# KELU1-0233.net
KiCad netlist of a schematic drawn in EAGLE
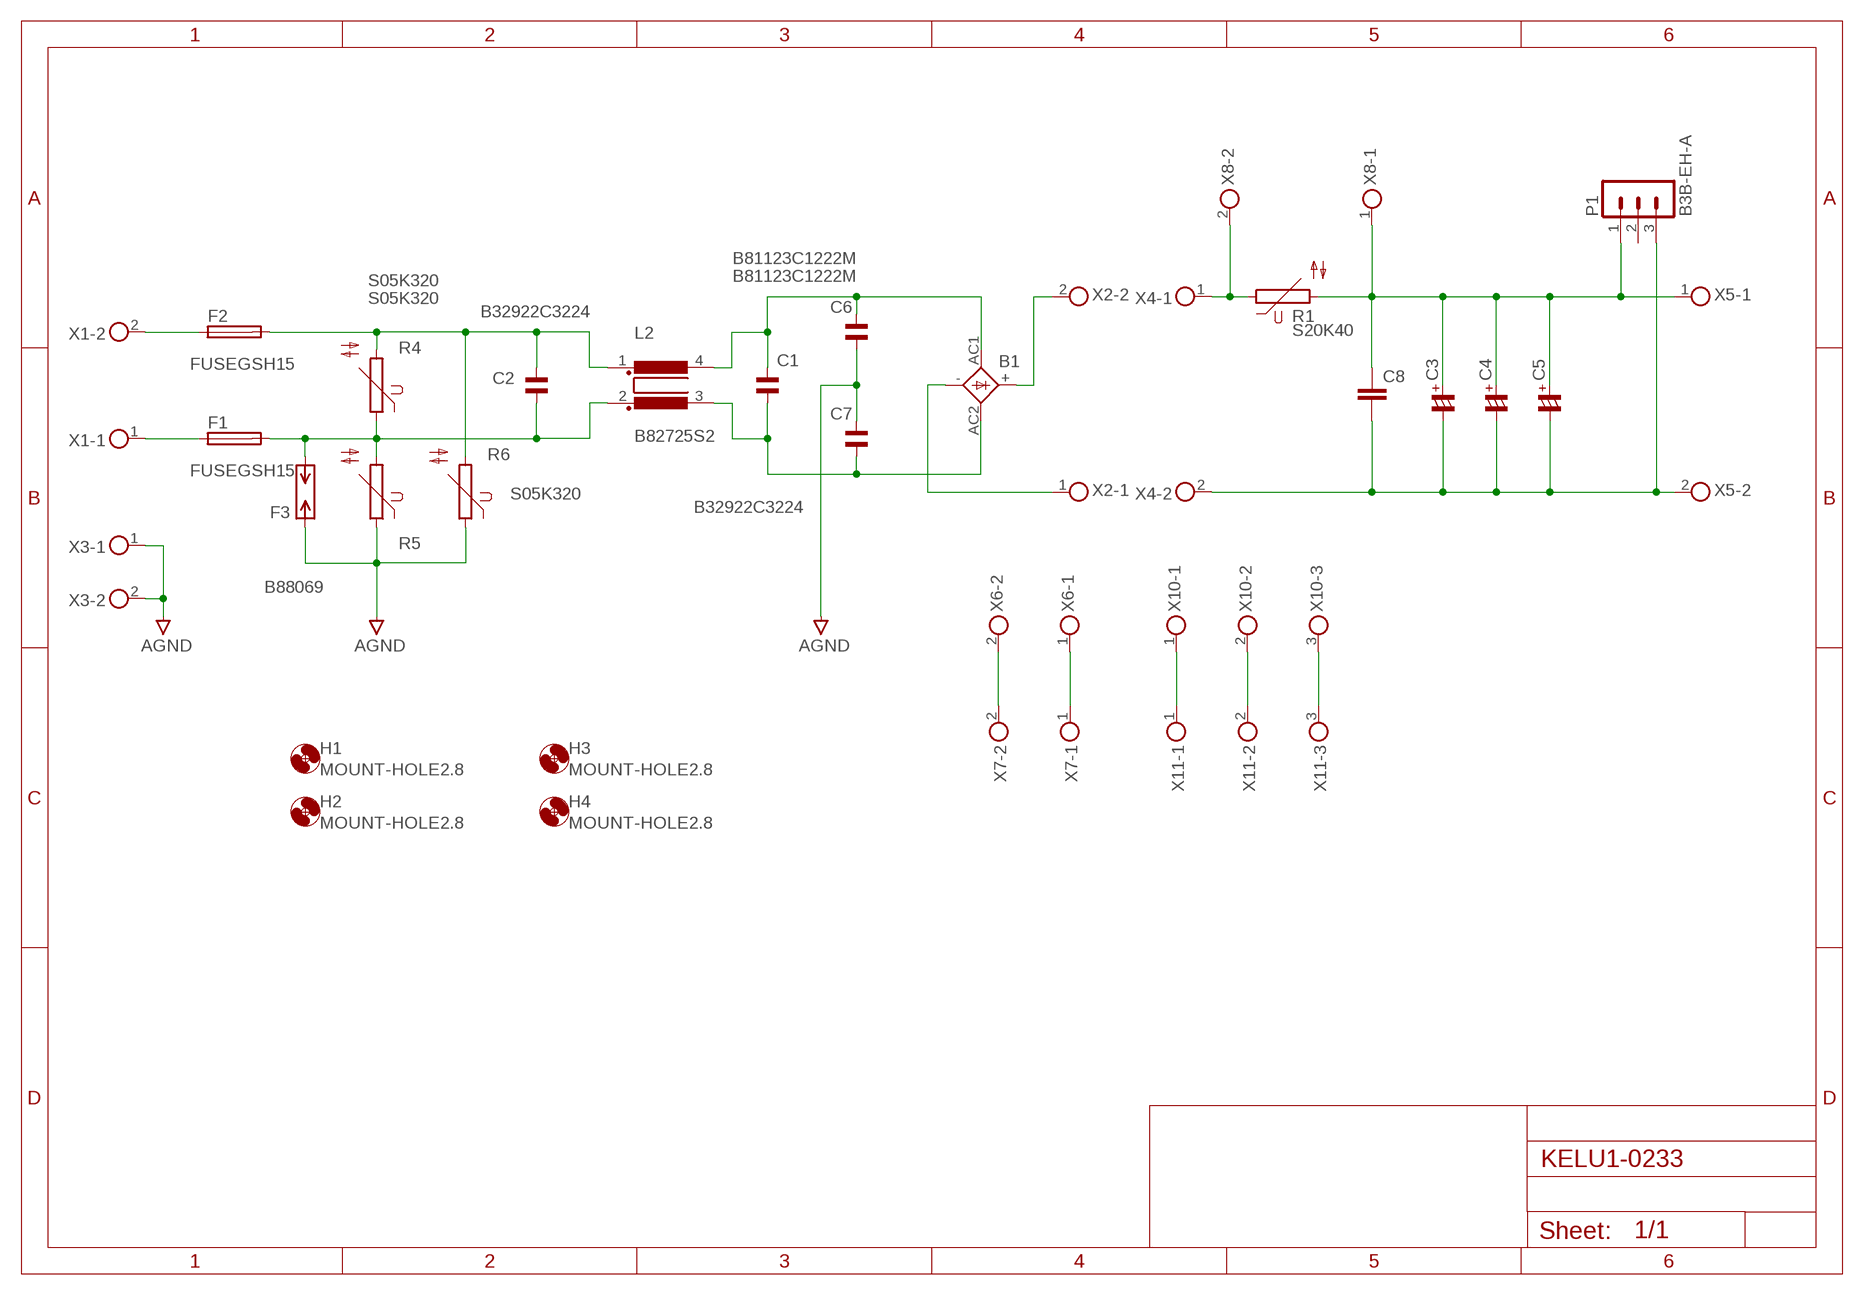
[diagram p0: schematic, sheet 1]

(export (version "E")
  (design (tool "Eeschema 10.0.6"))
  (components
    (comp (ref "B1")
      (value "FBM")
      (footprint "eagle-import:FBM")
      (libsource (lib "eagle-import") (part "FBM"))
    )
    (comp (ref "C1")
      (value "B32922C3224")
      (footprint "eagle-import:C150-054X183")
      (libsource (lib "eagle-import") (part "C-EU150-054X183"))
    )
    (comp (ref "C2")
      (value "B32922C3224")
      (footprint "eagle-import:C150-054X183")
      (libsource (lib "eagle-import") (part "C-EU150-054X183"))
    )
    (comp (ref "C3")
      (value "CPOL-EUE7.5-18")
      (footprint "eagle-import:E7,5-18")
      (libsource (lib "eagle-import") (part "CPOL-EUE7.5-18"))
    )
    (comp (ref "C4")
      (value "CPOL-EUE7.5-18")
      (footprint "eagle-import:E7,5-18")
      (libsource (lib "eagle-import") (part "CPOL-EUE7.5-18"))
    )
    (comp (ref "C5")
      (value "CPOL-EUE7.5-18")
      (footprint "eagle-import:E7,5-18")
      (libsource (lib "eagle-import") (part "CPOL-EUE7.5-18"))
    )
    (comp (ref "C6")
      (value "B81123C1222M")
      (footprint "eagle-import:C150-054X183")
      (libsource (lib "eagle-import") (part "C-EU150-054X183"))
    )
    (comp (ref "C7")
      (value "B81123C1222M")
      (footprint "eagle-import:C150-054X183")
      (libsource (lib "eagle-import") (part "C-EU150-054X183"))
    )
    (comp (ref "C8")
      (value "C-EU102-043X133")
      (footprint "eagle-import:C102-043X133")
      (libsource (lib "eagle-import") (part "resistor_C-EU102-043X133"))
    )
    (comp (ref "F1")
      (value "FUSEGSH15")
      (footprint "eagle-import:GSH15")
      (libsource (lib "eagle-import") (part "FUSEGSH15"))
    )
    (comp (ref "F2")
      (value "FUSEGSH15")
      (footprint "eagle-import:GSH15")
      (libsource (lib "eagle-import") (part "FUSEGSH15"))
    )
    (comp (ref "F3")
      (value "B88069")
      (footprint "eagle-import:N81")
      (libsource (lib "eagle-import") (part "B88069"))
    )
    (comp (ref "H1")
      (value "MOUNT-HOLE2.8")
      (footprint "eagle-import:2,8")
      (libsource (lib "eagle-import") (part "MOUNT-HOLE2.8"))
    )
    (comp (ref "H2")
      (value "MOUNT-HOLE2.8")
      (footprint "eagle-import:2,8")
      (libsource (lib "eagle-import") (part "MOUNT-HOLE2.8"))
    )
    (comp (ref "H3")
      (value "MOUNT-HOLE2.8")
      (footprint "eagle-import:2,8")
      (libsource (lib "eagle-import") (part "MOUNT-HOLE2.8"))
    )
    (comp (ref "H4")
      (value "MOUNT-HOLE2.8")
      (footprint "eagle-import:2,8")
      (libsource (lib "eagle-import") (part "MOUNT-HOLE2.8"))
    )
    (comp (ref "L2")
      (value "B82725S2")
      (footprint "eagle-import:PLC")
      (libsource (lib "eagle-import") (part "B82725S2"))
    )
    (comp (ref "P1")
      (value "B3B-EH-A")
      (footprint "eagle-import:B3B-EH-A")
      (libsource (lib "eagle-import") (part "B3B-EH-A"))
    )
    (comp (ref "R1")
      (value "S20K40")
      (footprint "eagle-import:S20K40")
      (libsource (lib "eagle-import") (part "S20K40"))
    )
    (comp (ref "R4")
      (value "S05K320")
      (footprint "eagle-import:S05K300")
      (libsource (lib "eagle-import") (part "S05K300"))
    )
    (comp (ref "R5")
      (value "S05K320")
      (footprint "eagle-import:S05K300")
      (libsource (lib "eagle-import") (part "S05K300"))
    )
    (comp (ref "R6")
      (value "S05K320")
      (footprint "eagle-import:S05K300")
      (libsource (lib "eagle-import") (part "S05K300"))
    )
    (comp (ref "X1")
      (value "DG129-7.5-02P")
      (footprint "eagle-import:DG129-7.5-02P-14-00A")
      (libsource (lib "eagle-import") (part "DG129-7.5-02P"))
    )
    (comp (ref "X2")
      (value "DG129-7.5-02P")
      (footprint "eagle-import:DG129-7.5-02P-14-00A")
      (libsource (lib "eagle-import") (part "DG129-7.5-02P"))
    )
    (comp (ref "X3")
      (value "DG129-7.5-02P")
      (footprint "eagle-import:DG129-7.5-02P-14-00A")
      (libsource (lib "eagle-import") (part "DG129-7.5-02P"))
    )
    (comp (ref "X4")
      (value "DG129-7.5-02P")
      (footprint "eagle-import:DG129-7.5-02P-14-00A")
      (libsource (lib "eagle-import") (part "DG129-7.5-02P"))
    )
    (comp (ref "X5")
      (value "DG129-7.5-02P")
      (footprint "eagle-import:DG129-7.5-02P-14-00A")
      (libsource (lib "eagle-import") (part "DG129-7.5-02P"))
    )
    (comp (ref "X6")
      (value "DG129-7.5-02P")
      (footprint "eagle-import:DG129-7.5-02P-14-00A")
      (libsource (lib "eagle-import") (part "DG129-7.5-02P"))
    )
    (comp (ref "X7")
      (value "DG129-7.5-02P")
      (footprint "eagle-import:DG129-7.5-02P-14-00A")
      (libsource (lib "eagle-import") (part "DG129-7.5-02P"))
    )
    (comp (ref "X8")
      (value "DG129-7.5-02P")
      (footprint "eagle-import:DG129-7.5-02P-14-00A")
      (libsource (lib "eagle-import") (part "DG129-7.5-02P"))
    )
    (comp (ref "X10")
      (value "DG129-7.5-03P")
      (footprint "eagle-import:DG129-7.5-03P-14-00A")
      (libsource (lib "eagle-import") (part "DG129-7.5-03P"))
    )
    (comp (ref "X11")
      (value "DG129-7.5-03P")
      (footprint "eagle-import:DG129-7.5-03P-14-00A")
      (libsource (lib "eagle-import") (part "DG129-7.5-03P"))
    )
  )
  (nets
    (net (code "1") (name "AGND") (class "Default")
      (node (ref "C6") (pin "2") (pinfunction "2_2") (pintype "passive"))
      (node (ref "C7") (pin "1") (pinfunction "1_1") (pintype "passive"))
      (node (ref "F3") (pin "P$1") (pinfunction "A_P$1") (pintype "bidirectional"))
      (node (ref "R5") (pin "1") (pinfunction "1_1") (pintype "passive"))
      (node (ref "R6") (pin "1") (pinfunction "1_1") (pintype "passive"))
      (node (ref "X3") (pin "1") (pinfunction "1_1") (pintype "passive"))
      (node (ref "X3") (pin "2") (pinfunction "1_2") (pintype "passive"))
    )
    (net (code "2") (name "Net-(B1-Pad-)") (class "Default")
      (node (ref "B1") (pin "-") (pinfunction "-_-") (pintype "passive"))
      (node (ref "X2") (pin "1") (pinfunction "1_1") (pintype "passive"))
    )
    (net (code "3") (name "Net-(B1-PadAC1)") (class "Default")
      (node (ref "B1") (pin "AC1") (pinfunction "AC1_AC1") (pintype "passive"))
      (node (ref "C1") (pin "1") (pinfunction "1_1") (pintype "passive"))
      (node (ref "C6") (pin "1") (pinfunction "1_1") (pintype "passive"))
      (node (ref "L2") (pin "4") (pinfunction "4_4") (pintype "passive"))
    )
    (net (code "4") (name "Net-(B1-PadAC2)") (class "Default")
      (node (ref "B1") (pin "AC2") (pinfunction "AC2_AC2") (pintype "passive"))
      (node (ref "C1") (pin "2") (pinfunction "2_2") (pintype "passive"))
      (node (ref "C7") (pin "2") (pinfunction "2_2") (pintype "passive"))
      (node (ref "L2") (pin "3") (pinfunction "3_3") (pintype "passive"))
    )
    (net (code "5") (name "Net-(C2-Pad1)") (class "Default")
      (node (ref "C2") (pin "1") (pinfunction "1_1") (pintype "passive"))
      (node (ref "F2") (pin "2") (pinfunction "2_2") (pintype "passive"))
      (node (ref "L2") (pin "1") (pinfunction "1_1") (pintype "passive"))
      (node (ref "R4") (pin "2") (pinfunction "2_2") (pintype "passive"))
      (node (ref "R6") (pin "2") (pinfunction "2_2") (pintype "passive"))
    )
    (net (code "6") (name "Net-(C3-Pad+)") (class "Default")
      (node (ref "C3") (pin "+") (pinfunction "+_+") (pintype "passive"))
      (node (ref "C4") (pin "+") (pinfunction "+_+") (pintype "passive"))
      (node (ref "C5") (pin "+") (pinfunction "+_+") (pintype "passive"))
      (node (ref "C8") (pin "1") (pinfunction "1_1") (pintype "passive"))
      (node (ref "P1") (pin "1") (pinfunction "1_1") (pintype "passive"))
      (node (ref "R1") (pin "2") (pinfunction "2_2") (pintype "passive"))
      (node (ref "X5") (pin "1") (pinfunction "1_1") (pintype "passive"))
      (node (ref "X8") (pin "1") (pinfunction "1_1") (pintype "passive"))
    )
    (net (code "7") (name "Net-(F1-Pad1)") (class "Default")
      (node (ref "F1") (pin "1") (pinfunction "1_1") (pintype "passive"))
      (node (ref "X1") (pin "1") (pinfunction "1_1") (pintype "passive"))
    )
    (net (code "8") (name "Net-(F3-B)") (class "Default")
      (node (ref "C2") (pin "2") (pinfunction "2_2") (pintype "passive"))
      (node (ref "F1") (pin "2") (pinfunction "2_2") (pintype "passive"))
      (node (ref "F3") (pin "P$2") (pinfunction "B_P$2") (pintype "bidirectional"))
      (node (ref "L2") (pin "2") (pinfunction "2_2") (pintype "passive"))
      (node (ref "R4") (pin "1") (pinfunction "1_1") (pintype "passive"))
      (node (ref "R5") (pin "2") (pinfunction "2_2") (pintype "passive"))
    )
    (net (code "9") (name "Net-(X1B-1)") (class "Default")
      (node (ref "F2") (pin "1") (pinfunction "1_1") (pintype "passive"))
      (node (ref "X1") (pin "2") (pinfunction "1_2") (pintype "passive"))
    )
    (net (code "10") (name "Net-(X2B-1)") (class "Default")
      (node (ref "B1") (pin "+") (pinfunction "+_+") (pintype "passive"))
      (node (ref "X2") (pin "2") (pinfunction "1_2") (pintype "passive"))
    )
    (net (code "11") (name "Net-(X4B-1)") (class "Default")
      (node (ref "C3") (pin "-") (pinfunction "-_-") (pintype "passive"))
      (node (ref "C4") (pin "-") (pinfunction "-_-") (pintype "passive"))
      (node (ref "C5") (pin "-") (pinfunction "-_-") (pintype "passive"))
      (node (ref "C8") (pin "2") (pinfunction "2_2") (pintype "passive"))
      (node (ref "P1") (pin "3") (pinfunction "3_3") (pintype "passive"))
      (node (ref "X4") (pin "2") (pinfunction "1_2") (pintype "passive"))
      (node (ref "X5") (pin "2") (pinfunction "1_2") (pintype "passive"))
    )
    (net (code "12") (name "Net-(X6-Pad1)") (class "Default")
      (node (ref "X6") (pin "1") (pinfunction "1_1") (pintype "passive"))
      (node (ref "X7") (pin "1") (pinfunction "1_1") (pintype "passive"))
    )
    (net (code "13") (name "Net-(X6B-1)") (class "Default")
      (node (ref "X6") (pin "2") (pinfunction "1_2") (pintype "passive"))
      (node (ref "X7") (pin "2") (pinfunction "1_2") (pintype "passive"))
    )
    (net (code "14") (name "Net-(X8B-1)") (class "Default")
      (node (ref "R1") (pin "1") (pinfunction "1_1") (pintype "passive"))
      (node (ref "X4") (pin "1") (pinfunction "1_1") (pintype "passive"))
      (node (ref "X8") (pin "2") (pinfunction "1_2") (pintype "passive"))
    )
    (net (code "15") (name "Net-(X10-Pad1)") (class "Default")
      (node (ref "X10") (pin "1") (pinfunction "1_1") (pintype "passive"))
      (node (ref "X11") (pin "1") (pinfunction "1_1") (pintype "passive"))
    )
    (net (code "16") (name "Net-(X10B-1)") (class "Default")
      (node (ref "X10") (pin "2") (pinfunction "1_2") (pintype "passive"))
      (node (ref "X11") (pin "2") (pinfunction "1_2") (pintype "passive"))
    )
    (net (code "17") (name "Net-(X10C-1)") (class "Default")
      (node (ref "X10") (pin "3") (pinfunction "1_3") (pintype "passive"))
      (node (ref "X11") (pin "3") (pinfunction "1_3") (pintype "passive"))
    )
    (net (code "18") (name "unconnected-(P1-Pad2)") (class "Default")
      (node (ref "P1") (pin "2") (pinfunction "2_2") (pintype "passive"))
    )
  )
)
